# Sheet1.net
KiCad netlist of a schematic drawn in Altium Designer
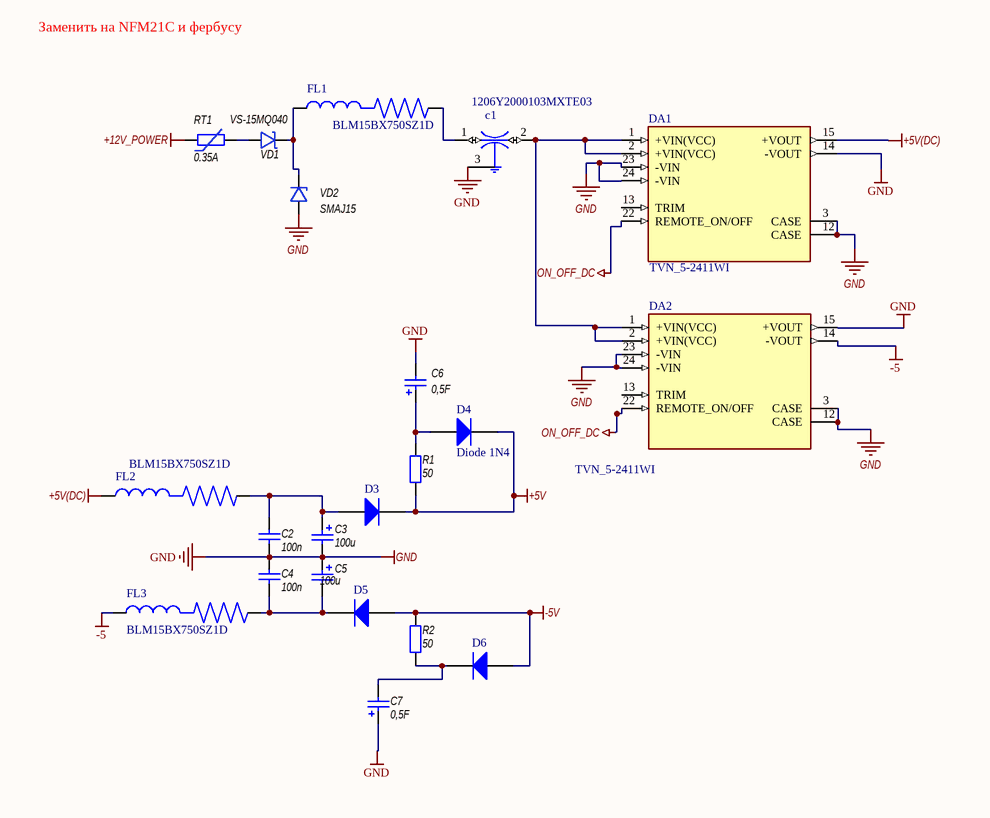
[diagram p0: Sheet1.SchDoc]

(export (version "E")
  (design (tool "Eeschema 10.0.6"))
  (components
    (comp (ref "c1")
      (value "1206Y2000103MXTE03")
      (footprint "FIL_NFM41PC155B1E3L")
      (description "ÐŸÐ¸Ñ‚Ð°Ð½Ð¸Ðµ Ñ‡ÐµÑ€ÐµÐ· ÐºÐ¾Ð½Ð´ÐµÐ½ÑÐ°Ñ‚Ð¾Ñ€Ñ‹ 1206 200Ð’ .01uF 20% X7R X2y Ñ„Ð¸Ð»ÑŒÑ‚Ñ€")
      (fields (field (name "MF") "Syfer"))
      (libsource (lib "1206Y2000103MXTE03") (part "1206Y2000103MXTE03"))
    )
    (comp (ref "C2") (value "100n") (footprint "CAP_0603") (libsource (lib "All") (part "_capacitor")))
    (comp (ref "C3")
      (value "100u")
      (footprint "CAPPM7343X310N")
      (libsource (lib "my-lib") (part "_capacitor_pol"))
    )
    (comp (ref "C4") (value "100n") (footprint "CAP_0603") (libsource (lib "my-lib") (part "_capacitor")))
    (comp (ref "C5")
      (value "100u")
      (footprint "CAPPM7343X310N")
      (libsource (lib "my-lib") (part "_capacitor_pol"))
    )
    (comp (ref "C6")
      (value "0,5F")
      (footprint "EECF5R5U474, 0.470 Ф, 5.5 В, 5мм")
      (libsource (lib "my-lib") (part "_capacitor_pol"))
    )
    (comp (ref "C7")
      (value "0,5F")
      (footprint "EECF5R5U474, 0.470 Ф, 5.5 В, 5мм")
      (libsource (lib "my-lib") (part "_capacitor_pol"))
    )
    (comp (ref "D3")
      (value "~")
      (footprint "DO-214AC (SMA)")
      (description "1 Amp Fast Recovery Rectifier")
      (fields (field (name "PUBLISHER") "Altium Limited"))
      (libsource (lib "Miscellaneous Devices") (part "Diode 1N4934"))
    )
    (comp (ref "D4")
      (value "Diode 1N4")
      (footprint "DO-214AC (SMA)")
      (description "1 Amp Fast Recovery Rectifier")
      (fields (field (name "PUBLISHER") "Altium Limited"))
      (libsource (lib "Miscellaneous Devices") (part "Diode 1N4934"))
    )
    (comp (ref "D5")
      (value "~")
      (footprint "DO-214AC (SMA)")
      (description "1 Amp Fast Recovery Rectifier")
      (fields (field (name "PUBLISHER") "Altium Limited"))
      (libsource (lib "Miscellaneous Devices") (part "Diode 1N4934"))
    )
    (comp (ref "D6")
      (value "~")
      (footprint "DO-214AC (SMA)")
      (description "1 Amp Fast Recovery Rectifier")
      (fields (field (name "PUBLISHER") "Altium Limited"))
      (libsource (lib "Miscellaneous Devices") (part "Diode 1N4934"))
    )
    (comp (ref "DA1")
      (value "TVN_5-2411WI")
      (footprint "CONV_TVN_5-2415WI")
      (description "Isolated Module DC DC Converter 1 Output 24V    208mA 9V - 36V Input")
      (fields (field (name "MF") "Traco Power") (field (name "MP") "TVN 5-2415WI"))
      (libsource (lib "TVN_5-2415WI") (part "TVN_5-2415WI"))
    )
    (comp (ref "DA2")
      (value "TVN_5-2411WI")
      (footprint "CONV_TVN_5-2415WI")
      (description "Isolated Module DC DC Converter 1 Output 24V    208mA 9V - 36V Input")
      (fields (field (name "MF") "Traco Power") (field (name "MP") "TVN 5-2415WI"))
      (libsource (lib "TVN_5-2415WI") (part "TVN_5-2415WI"))
    )
    (comp (ref "FL1")
      (value "BLM15BX750SZ1D")
      (footprint "BEADC2012X105N")
      (description "Ñ„ÐµÑ€Ñ€Ð¸Ñ‚Ð¾Ð²Ð°Ñ ÑˆÐ°Ð¹Ð±Ð°")
      (fields (field (name "MF") "Murata"))
      (libsource (lib "BLM15BX750SZ1D") (part "BLM15BX750SZ1D"))
    )
    (comp (ref "FL2")
      (value "BLM15BX750SZ1D")
      (footprint "BEADC2012X105N")
      (description "Ñ„ÐµÑ€Ñ€Ð¸Ñ‚Ð¾Ð²Ð°Ñ ÑˆÐ°Ð¹Ð±Ð°")
      (fields (field (name "MF") "Murata"))
      (libsource (lib "BLM15BX750SZ1D") (part "BLM15BX750SZ1D"))
    )
    (comp (ref "FL3")
      (value "BLM15BX750SZ1D")
      (footprint "BEADC2012X105N")
      (description "Ñ„ÐµÑ€Ñ€Ð¸Ñ‚Ð¾Ð²Ð°Ñ ÑˆÐ°Ð¹Ð±Ð°")
      (fields (field (name "MF") "Murata"))
      (libsource (lib "BLM15BX750SZ1D") (part "BLM15BX750SZ1D"))
    )
    (comp (ref "R1") (value "50") (footprint "RES_0805") (libsource (lib "my-lib") (part "_resistor")))
    (comp (ref "R2") (value "50") (footprint "RES_0805") (libsource (lib "my-lib") (part "_resistor")))
    (comp (ref "RT1")
      (value "0.35A")
      (footprint "FUSER_MF-MSMF200-2")
      (libsource (lib "my-lib") (part "_termistor"))
    )
    (comp (ref "VD1")
      (value "VS-15MQ040")
      (footprint "DO-214AC (SMA)")
      (libsource (lib "my-lib") (part "_diod_schottky"))
    )
    (comp (ref "VD2")
      (value "SMAJ15")
      (footprint "DO-214AC (SMA)")
      (libsource (lib "my-lib") (part "_diode_zener"))
    )
  )
  (nets
    (net (code "1") (name "+5V") (class "Default")
      (node (ref "D3") (pin "k") (pinfunction "2_k") (pintype "passive"))
      (node (ref "D4") (pin "k") (pinfunction "2_k") (pintype "passive"))
      (node (ref "R1") (pin "1") (pinfunction "1_1") (pintype "passive"))
    )
    (net (code "2") (name "+5V(DC)") (class "Default")
      (node (ref "DA1") (pin "15") (pinfunction "+VOUT_15") (pintype "output"))
      (node (ref "FL2") (pin "1") (pinfunction "1_1") (pintype "passive"))
    )
    (net (code "3") (name "+12V_POWER") (class "Default")
      (node (ref "RT1") (pin "1") (pinfunction "1_1") (pintype "passive"))
    )
    (net (code "4") (name "-5") (class "Default")
      (node (ref "DA2") (pin "14") (pinfunction "-VOUT_14") (pintype "output"))
      (node (ref "FL3") (pin "1") (pinfunction "1_1") (pintype "passive"))
    )
    (net (code "5") (name "-5V") (class "Default")
      (node (ref "D5") (pin "a") (pinfunction "1_a") (pintype "passive"))
      (node (ref "D6") (pin "a") (pinfunction "1_a") (pintype "passive"))
      (node (ref "R2") (pin "2") (pinfunction "2_2") (pintype "passive"))
    )
    (net (code "6") (name "GND") (class "Default")
      (node (ref "C2") (pin "1") (pinfunction "1_1") (pintype "passive"))
      (node (ref "C3") (pin "2") (pinfunction "2_2") (pintype "passive"))
      (node (ref "C4") (pin "2") (pinfunction "2_2") (pintype "passive"))
      (node (ref "C5") (pin "1") (pinfunction "1_1") (pintype "passive"))
      (node (ref "C6") (pin "2") (pinfunction "2_2") (pintype "passive"))
      (node (ref "C7") (pin "1") (pinfunction "1_1") (pintype "passive"))
      (node (ref "DA1") (pin "12") (pinfunction "CASE_12") (pintype "power_in"))
      (node (ref "DA1") (pin "14") (pinfunction "-VOUT_14") (pintype "output"))
      (node (ref "DA1") (pin "23") (pinfunction "-VIN_23") (pintype "input"))
      (node (ref "DA1") (pin "24") (pinfunction "-VIN_24") (pintype "input"))
      (node (ref "DA1") (pin "3") (pinfunction "CASE_3") (pintype "power_in"))
      (node (ref "DA2") (pin "12") (pinfunction "CASE_12") (pintype "power_in"))
      (node (ref "DA2") (pin "15") (pinfunction "+VOUT_15") (pintype "output"))
      (node (ref "DA2") (pin "23") (pinfunction "-VIN_23") (pintype "input"))
      (node (ref "DA2") (pin "24") (pinfunction "-VIN_24") (pintype "input"))
      (node (ref "DA2") (pin "3") (pinfunction "CASE_3") (pintype "power_in"))
      (node (ref "VD2") (pin "a") (pinfunction "A_a") (pintype "passive"))
      (node (ref "c1") (pin "3") (pinfunction "GND_3") (pintype "power_in"))
    )
    (net (code "7") (name "Net-(D3-1)") (class "Default")
      (node (ref "C2") (pin "2") (pinfunction "2_2") (pintype "passive"))
      (node (ref "C3") (pin "1") (pinfunction "1_1") (pintype "passive"))
      (node (ref "D3") (pin "a") (pinfunction "1_a") (pintype "passive"))
      (node (ref "FL2") (pin "2") (pinfunction "2_2") (pintype "passive"))
    )
    (net (code "8") (name "Net-(D4-1)") (class "Default")
      (node (ref "C6") (pin "1") (pinfunction "1_1") (pintype "passive"))
      (node (ref "D4") (pin "a") (pinfunction "1_a") (pintype "passive"))
      (node (ref "R1") (pin "2") (pinfunction "2_2") (pintype "passive"))
    )
    (net (code "9") (name "Net-(D5-2)") (class "Default")
      (node (ref "C4") (pin "1") (pinfunction "1_1") (pintype "passive"))
      (node (ref "C5") (pin "2") (pinfunction "2_2") (pintype "passive"))
      (node (ref "D5") (pin "k") (pinfunction "2_k") (pintype "passive"))
      (node (ref "FL3") (pin "2") (pinfunction "2_2") (pintype "passive"))
    )
    (net (code "10") (name "Net-(D6-2)") (class "Default")
      (node (ref "C7") (pin "2") (pinfunction "2_2") (pintype "passive"))
      (node (ref "D6") (pin "k") (pinfunction "2_k") (pintype "passive"))
      (node (ref "R2") (pin "1") (pinfunction "1_1") (pintype "passive"))
    )
    (net (code "11") (name "Net-(VD1-A)") (class "Default")
      (node (ref "RT1") (pin "2") (pinfunction "2_2") (pintype "passive"))
      (node (ref "VD1") (pin "a") (pinfunction "A_a") (pintype "passive"))
    )
    (net (code "12") (name "Net-(VD1-K)") (class "Default")
      (node (ref "FL1") (pin "1") (pinfunction "1_1") (pintype "passive"))
      (node (ref "VD1") (pin "k") (pinfunction "K_k") (pintype "passive"))
      (node (ref "VD2") (pin "k") (pinfunction "K_k") (pintype "passive"))
    )
    (net (code "13") (name "Net-(c1-A)") (class "Default")
      (node (ref "FL1") (pin "2") (pinfunction "2_2") (pintype "passive"))
      (node (ref "c1") (pin "1") (pinfunction "A_1") (pintype "bidirectional"))
    )
    (net (code "14") (name "Net-(c1-B)") (class "Default")
      (node (ref "DA1") (pin "1") (pinfunction "+VIN(VCC)_1") (pintype "input"))
      (node (ref "DA1") (pin "2") (pinfunction "+VIN(VCC)_2") (pintype "input"))
      (node (ref "DA2") (pin "1") (pinfunction "+VIN(VCC)_1") (pintype "input"))
      (node (ref "DA2") (pin "2") (pinfunction "+VIN(VCC)_2") (pintype "input"))
      (node (ref "c1") (pin "2") (pinfunction "B_2") (pintype "bidirectional"))
    )
    (net (code "15") (name "ON_OFF_DC") (class "Default")
      (node (ref "DA1") (pin "22") (pinfunction "REMOTE_ON/OFF_22") (pintype "input"))
      (node (ref "DA2") (pin "22") (pinfunction "REMOTE_ON/OFF_22") (pintype "input"))
    )
    (net (code "16") (name "unconnected-(DA1-TRIM-Pad13)") (class "Default")
      (node (ref "DA1") (pin "13") (pinfunction "TRIM_13") (pintype "input"))
    )
    (net (code "17") (name "unconnected-(DA2-TRIM-Pad13)") (class "Default")
      (node (ref "DA2") (pin "13") (pinfunction "TRIM_13") (pintype "input"))
    )
  )
)
